# control_avr_rev_a.net
KiCad netlist of a schematic drawn in EAGLE
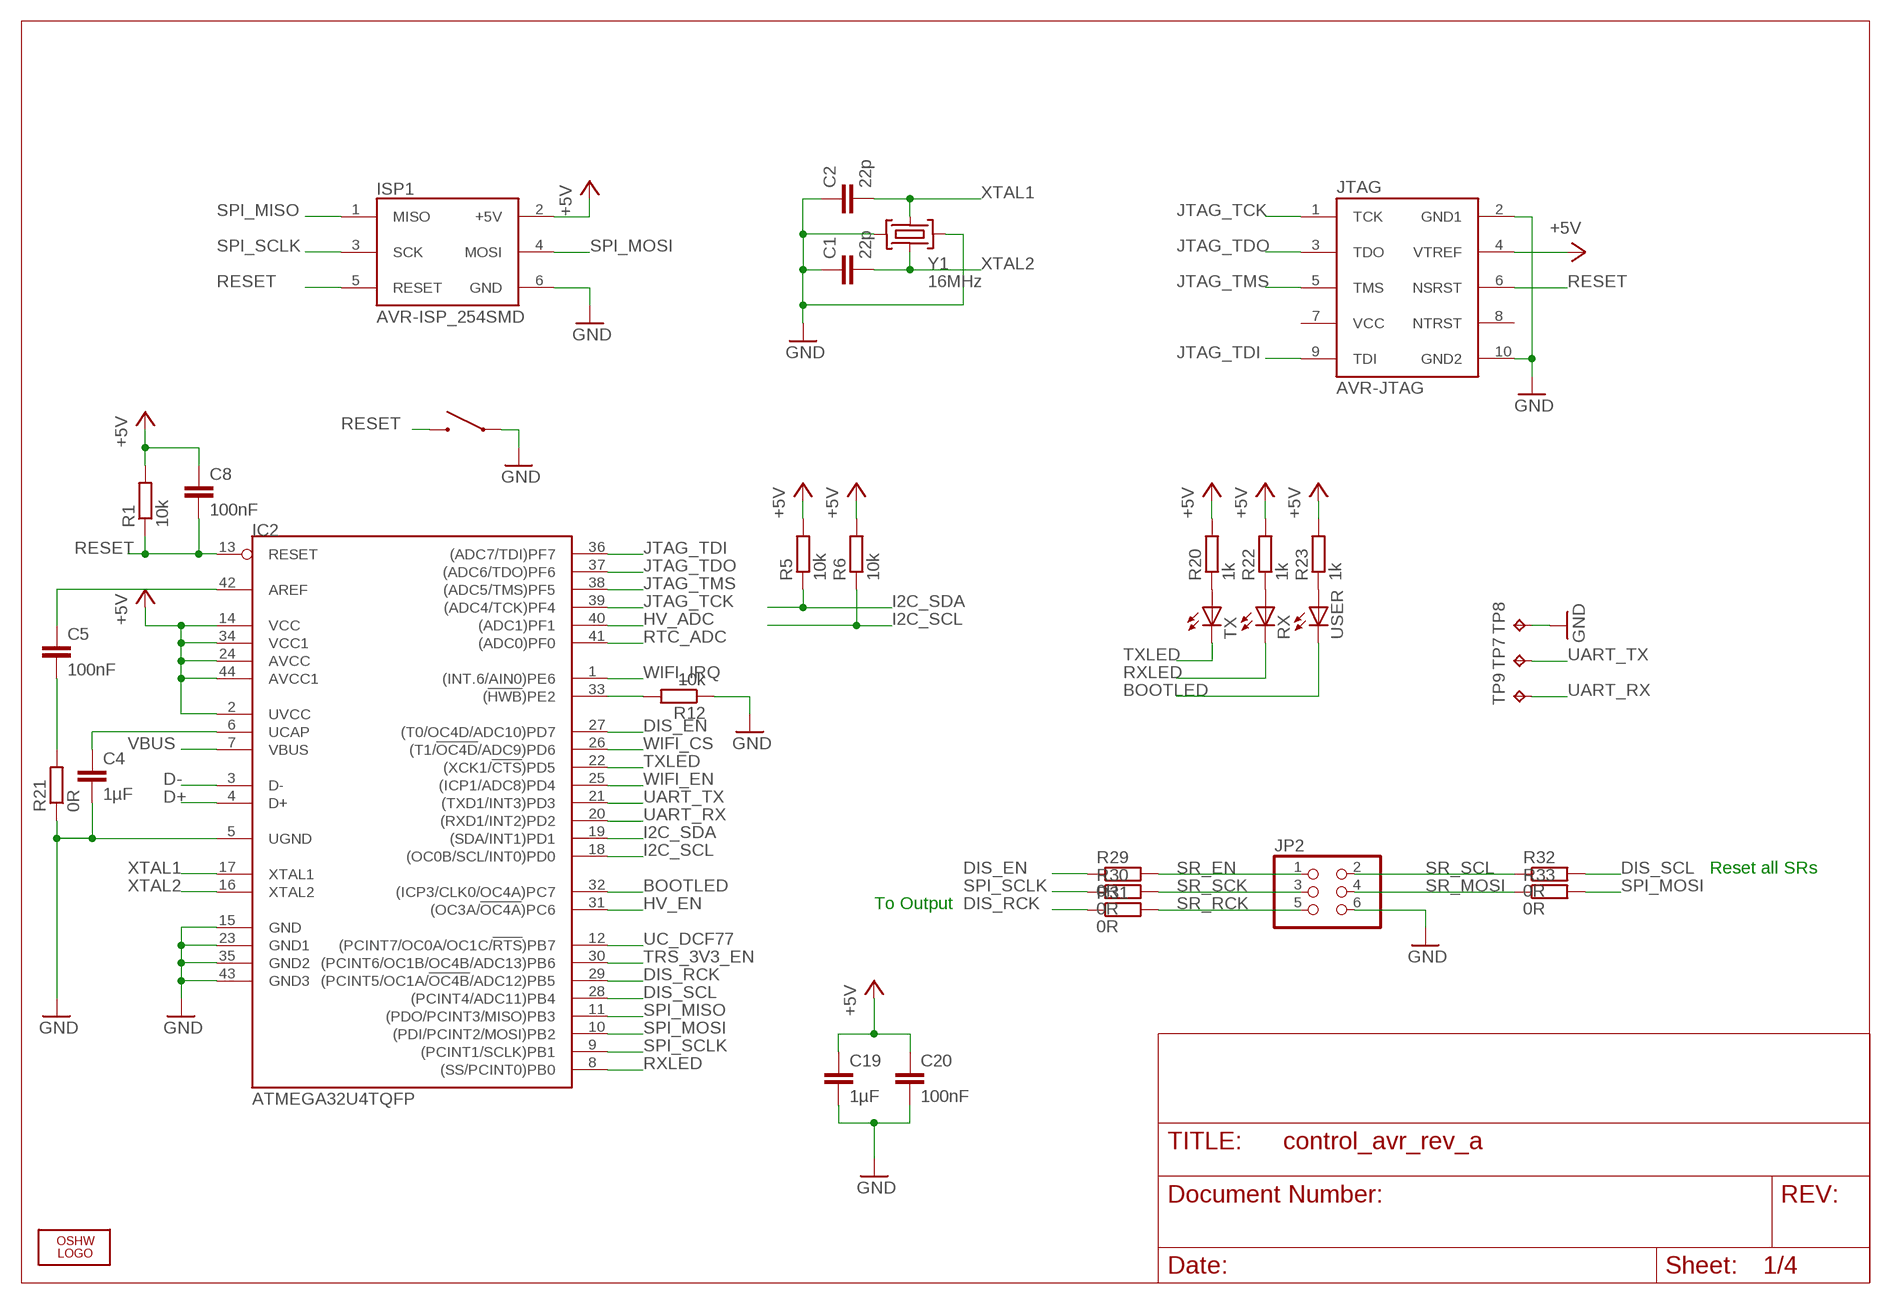
[diagram p0: schematic, sheet 1]
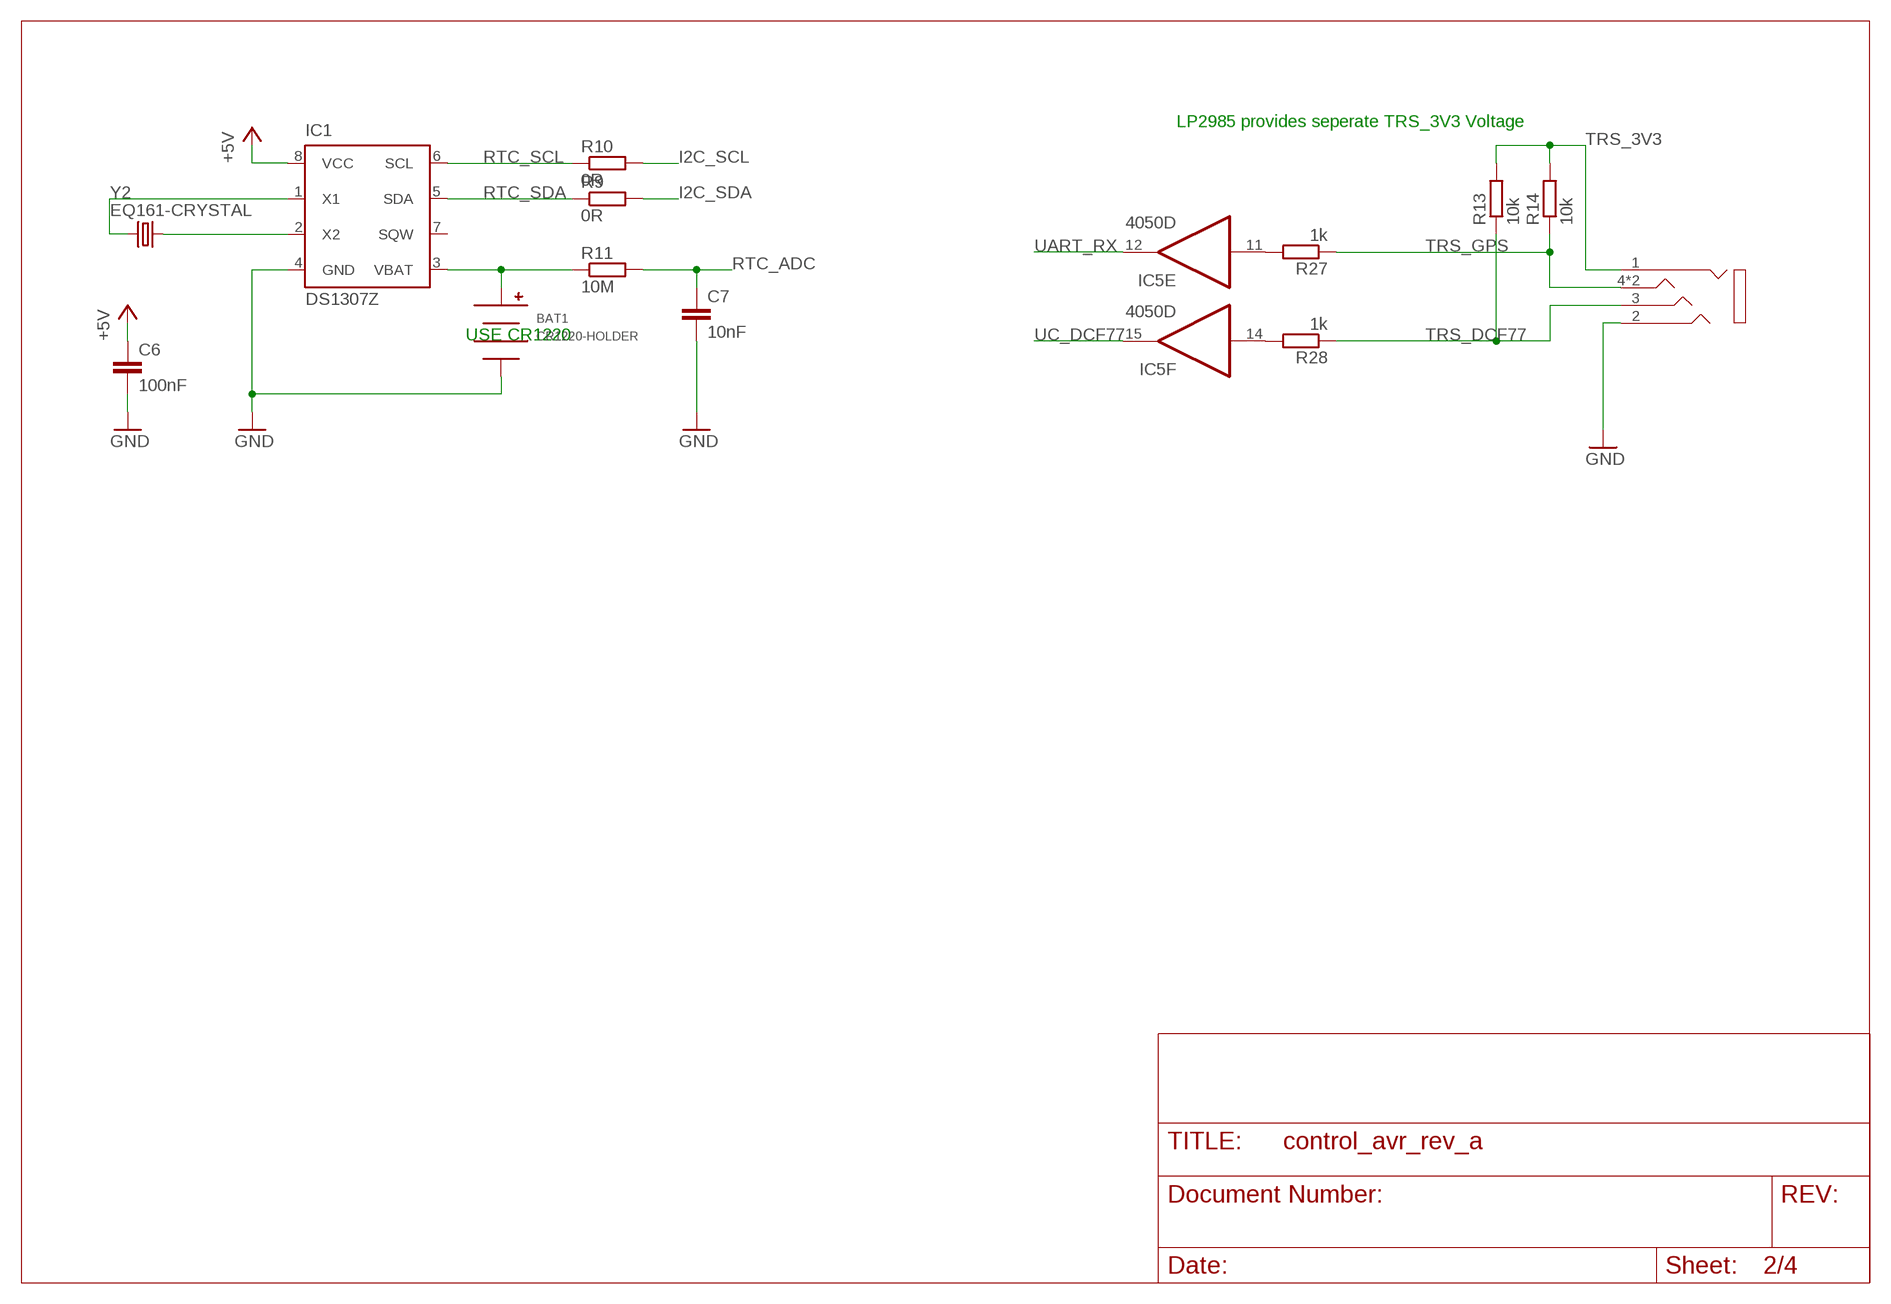
[diagram p1: schematic, sheet 2]
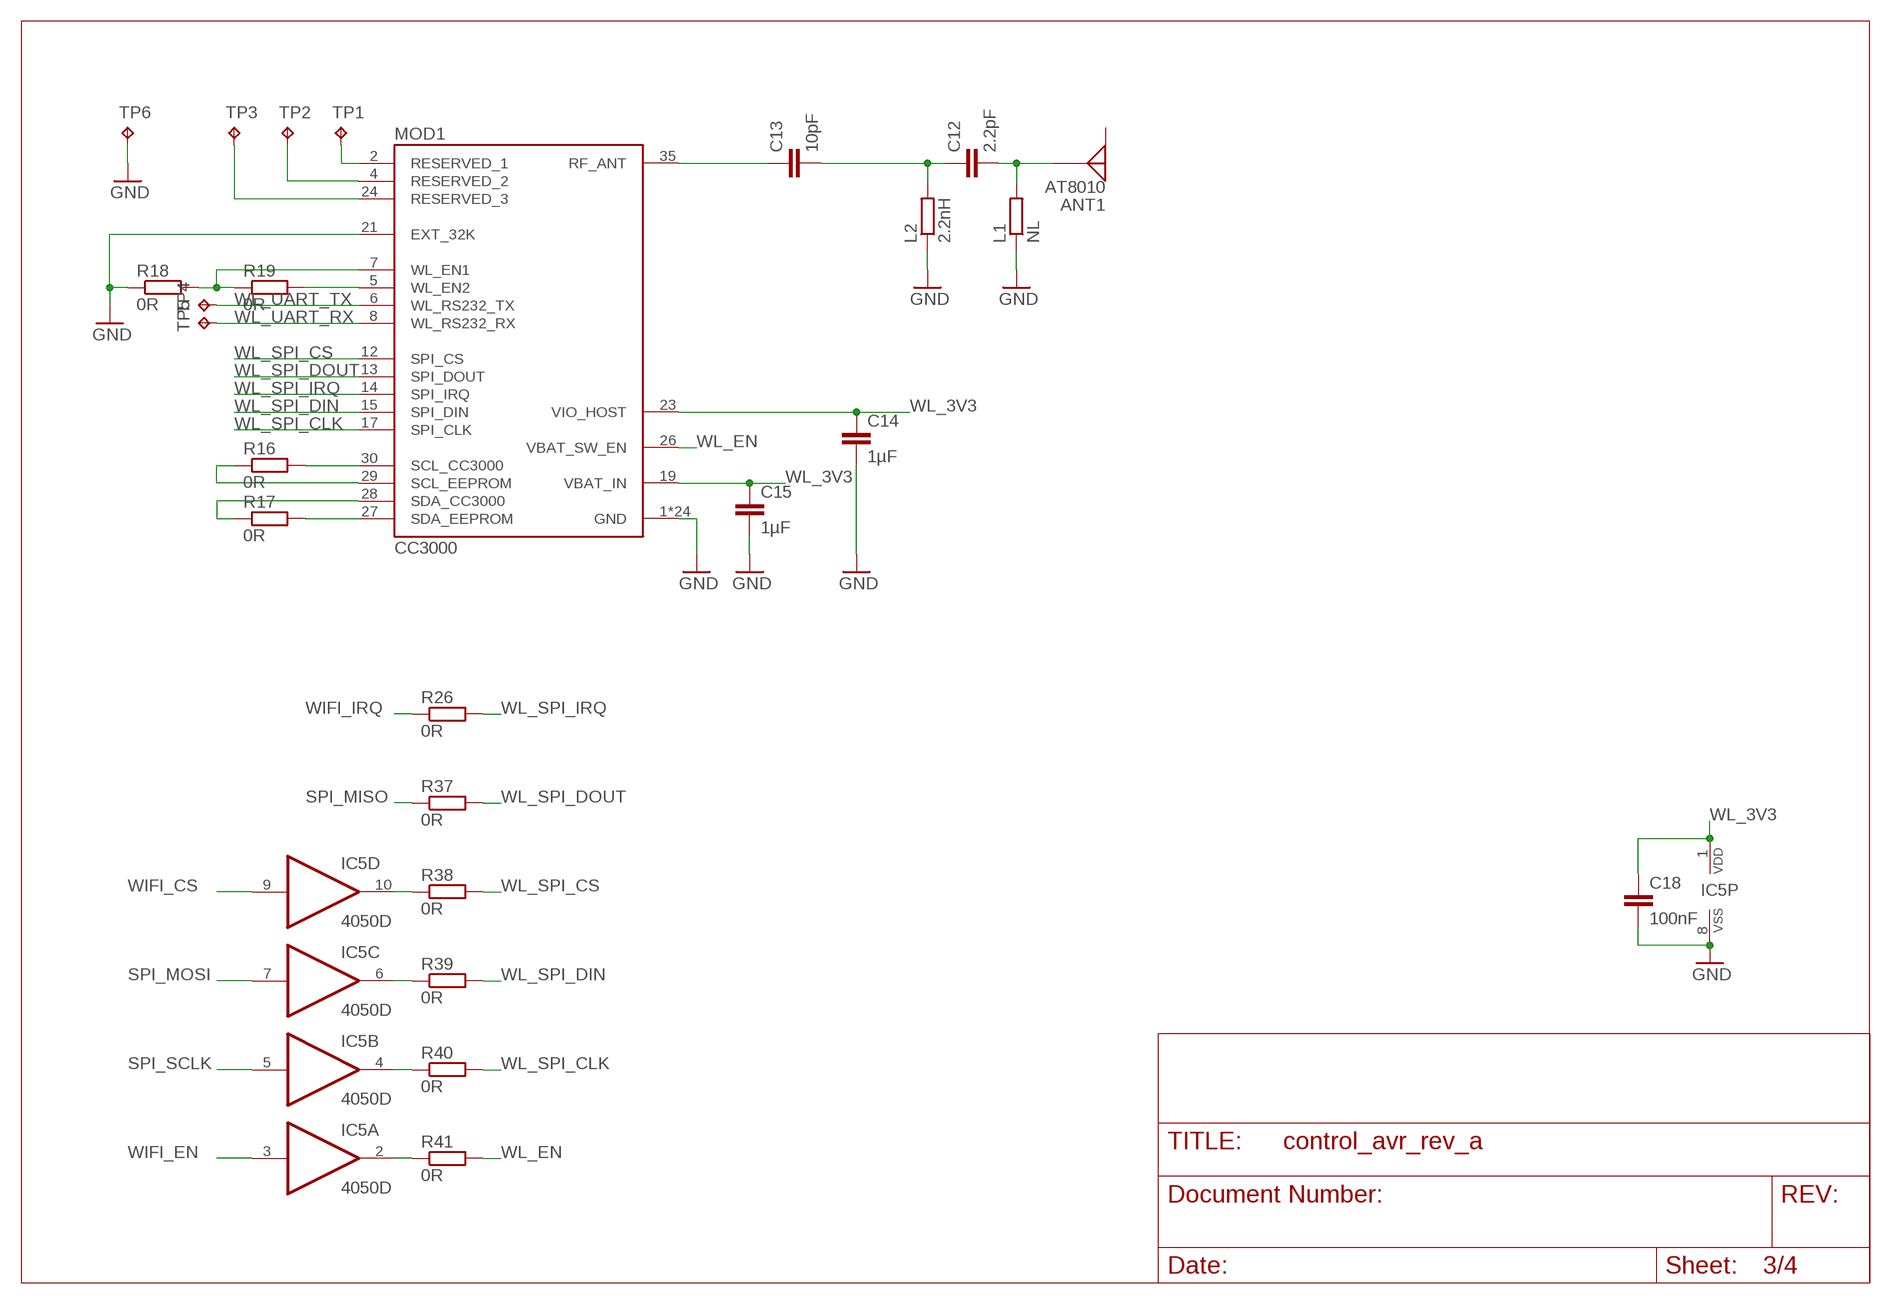
[diagram p2: schematic, sheet 3]
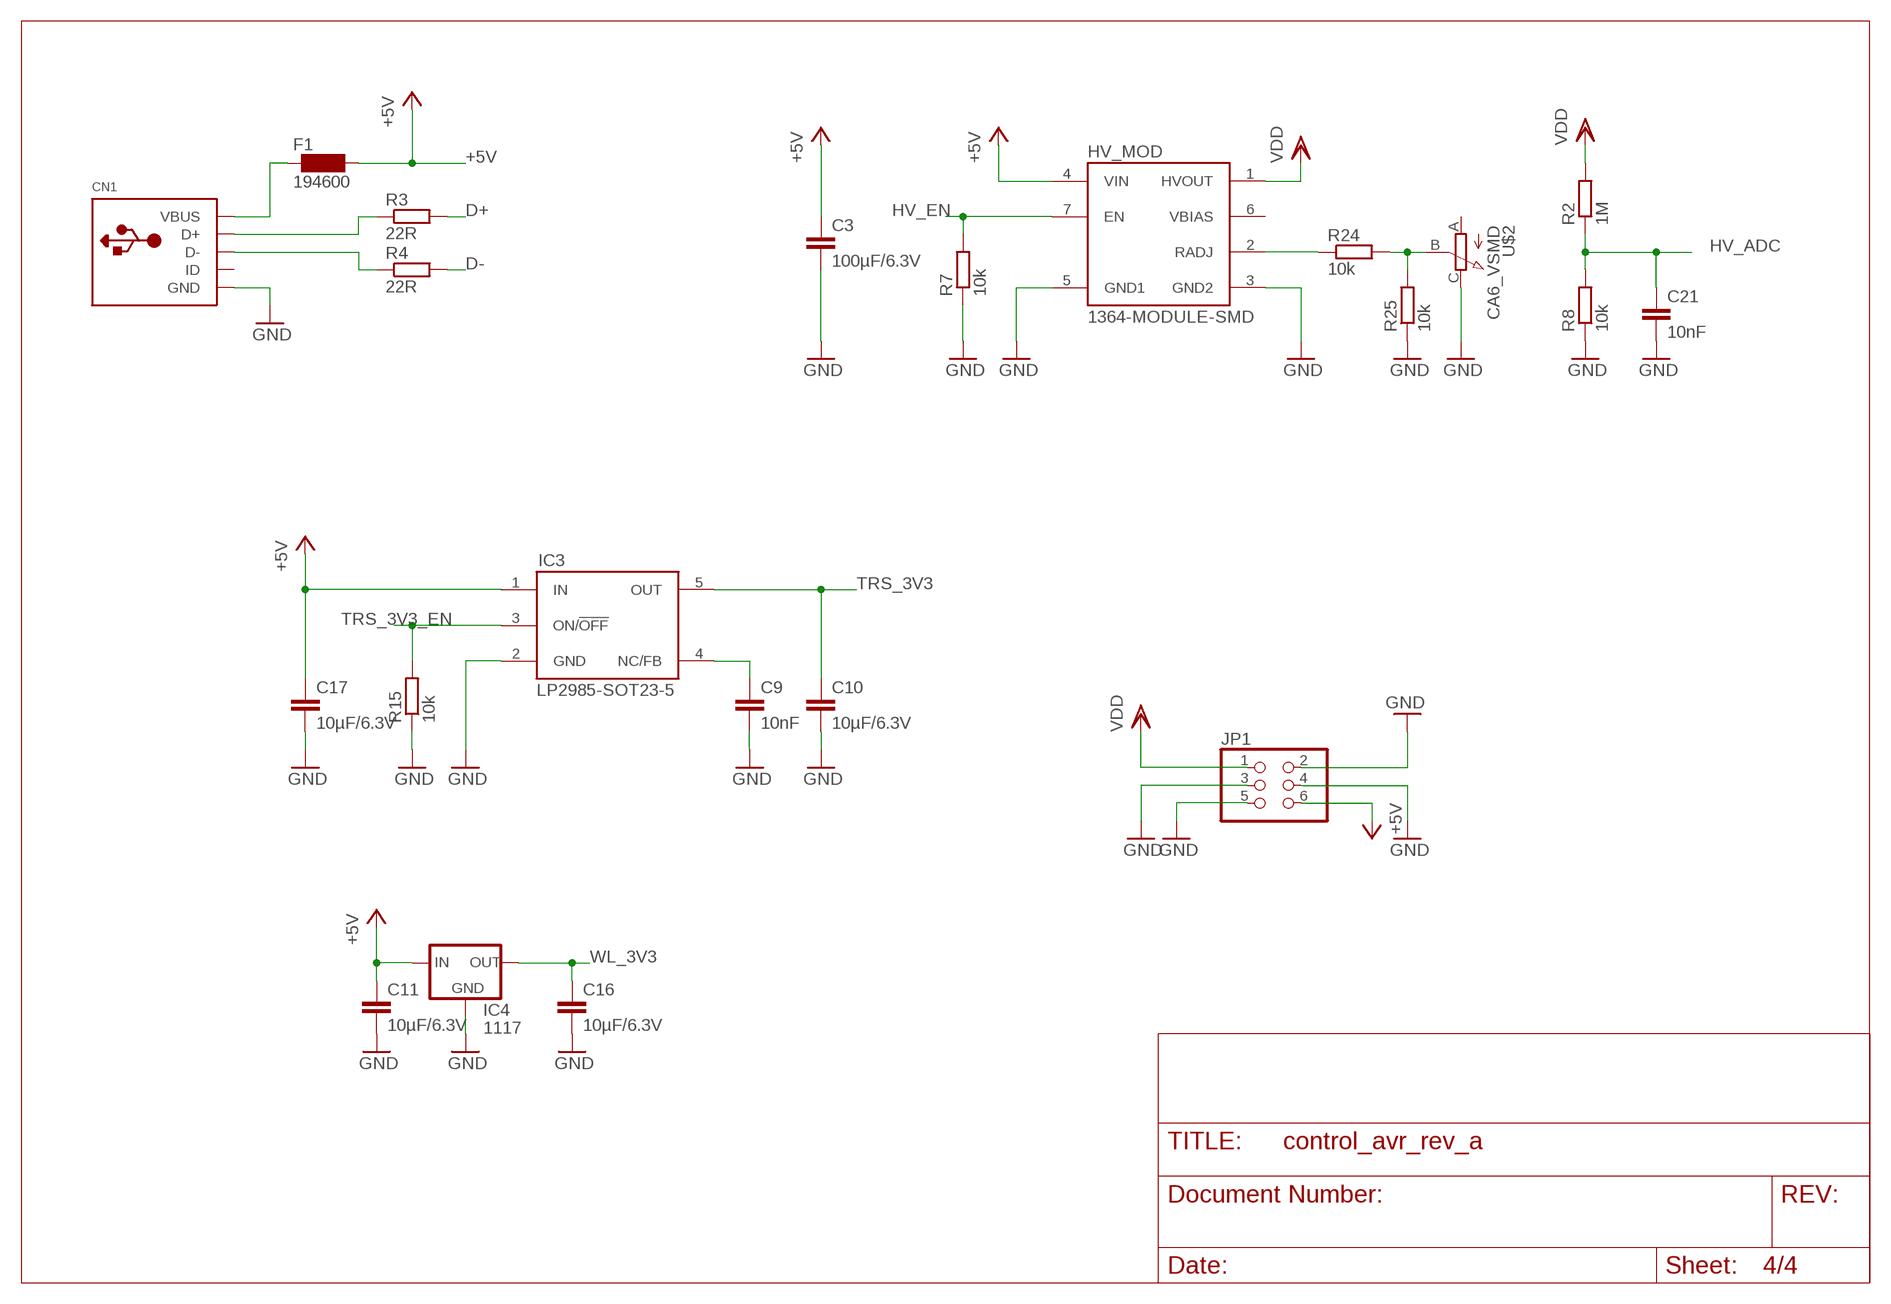
[diagram p3: schematic, sheet 4]

(export (version "E")
  (design (tool "Eeschema 10.0.6"))
  (components
    (comp (ref "C3")
      (value "100µF/6.3V")
      (footprint "eagle-import:C1210")
      (libsource (lib "eagle-import") (part "C-EUC1210"))
    )
    (comp (ref "C9")
      (value "10nF")
      (footprint "eagle-import:C0603")
      (libsource (lib "eagle-import") (part "C-EUC0603"))
    )
    (comp (ref "C10")
      (value "10µF/6.3V")
      (footprint "eagle-import:C0603")
      (libsource (lib "eagle-import") (part "C-EUC0603"))
    )
    (comp (ref "C11")
      (value "10µF/6.3V")
      (footprint "eagle-import:C0603")
      (libsource (lib "eagle-import") (part "C-EUC0603"))
    )
    (comp (ref "C16")
      (value "10µF/6.3V")
      (footprint "eagle-import:C0603")
      (libsource (lib "eagle-import") (part "C-EUC0603"))
    )
    (comp (ref "C17")
      (value "10µF/6.3V")
      (footprint "eagle-import:C0603")
      (libsource (lib "eagle-import") (part "C-EUC0603"))
    )
    (comp (ref "C21")
      (value "10nF")
      (footprint "eagle-import:C0603")
      (libsource (lib "eagle-import") (part "C-EUC0603"))
    )
    (comp (ref "CN1")
      (value "USBMINIB")
      (footprint "eagle-import:USB-MINIB")
      (libsource (lib "eagle-import") (part "USBMINIB"))
    )
    (comp (ref "F1")
      (value "194600")
      (footprint "eagle-import:1812")
      (libsource (lib "eagle-import") (part "194600"))
    )
    (comp (ref "HV_MOD")
      (value "1364-MODULE-SMD")
      (footprint "eagle-import:1364-SMD")
      (libsource (lib "eagle-import") (part "1364-MODULE-SMD"))
    )
    (comp (ref "IC3")
      (value "LP2985-SOT23-5")
      (footprint "eagle-import:SOT23-5")
      (libsource (lib "eagle-import") (part "LP2985-SOT23-5"))
    )
    (comp (ref "IC4")
      (value "1117")
      (footprint "eagle-import:SOT223")
      (libsource (lib "eagle-import") (part "1117"))
    )
    (comp (ref "JP1")
      (value "PINHD-2X3_2.54-SMD-R")
      (footprint "eagle-import:2X03SMD_R")
      (libsource (lib "eagle-import") (part "PINHD-2X3_2.54-SMD-R"))
    )
    (comp (ref "R2")
      (value "1M")
      (footprint "eagle-import:R1206")
      (libsource (lib "eagle-import") (part "R-EU_R1206"))
    )
    (comp (ref "R3")
      (value "22R")
      (footprint "eagle-import:R0603")
      (libsource (lib "eagle-import") (part "R-EU_R0603"))
    )
    (comp (ref "R4")
      (value "22R")
      (footprint "eagle-import:R0603")
      (libsource (lib "eagle-import") (part "R-EU_R0603"))
    )
    (comp (ref "R7")
      (value "10k")
      (footprint "eagle-import:R0603")
      (libsource (lib "eagle-import") (part "R-EU_R0603"))
    )
    (comp (ref "R8")
      (value "10k")
      (footprint "eagle-import:R0603")
      (libsource (lib "eagle-import") (part "R-EU_R0603"))
    )
    (comp (ref "R15")
      (value "10k")
      (footprint "eagle-import:R0603")
      (libsource (lib "eagle-import") (part "R-EU_R0603"))
    )
    (comp (ref "R24")
      (value "10k")
      (footprint "eagle-import:R0603")
      (libsource (lib "eagle-import") (part "R-EU_R0603"))
    )
    (comp (ref "R25")
      (value "10k")
      (footprint "eagle-import:R0603")
      (libsource (lib "eagle-import") (part "R-EU_R0603"))
    )
    (comp (ref "U$2")
      (value "CA6_VSMD")
      (footprint "eagle-import:CA6-VSMD")
      (libsource (lib "eagle-import") (part "CA6_VSMD"))
    )
    (comp (ref "ANT1")
      (value "AT8010")
      (footprint "eagle-import:AT8010")
      (libsource (lib "eagle-import") (part "AT8010"))
    )
    (comp (ref "C12")
      (value "2.2pF")
      (footprint "eagle-import:C0402")
      (libsource (lib "eagle-import") (part "C-EUC0402"))
    )
    (comp (ref "C13")
      (value "10pF")
      (footprint "eagle-import:C0402")
      (libsource (lib "eagle-import") (part "C-EUC0402"))
    )
    (comp (ref "C14")
      (value "1µF")
      (footprint "eagle-import:C0603")
      (libsource (lib "eagle-import") (part "C-EUC0603"))
    )
    (comp (ref "C15")
      (value "1µF")
      (footprint "eagle-import:C0603")
      (libsource (lib "eagle-import") (part "C-EUC0603"))
    )
    (comp (ref "C18")
      (value "100nF")
      (footprint "eagle-import:C0603")
      (libsource (lib "eagle-import") (part "C-EUC0603"))
    )
    (comp (ref "IC5")
      (value "4050D")
      (footprint "eagle-import:SO16")
      (libsource (lib "eagle-import") (part "4050D"))
    )
    (comp (ref "L1")
      (value "NL")
      (footprint "eagle-import:R0402")
      (libsource (lib "eagle-import") (part "R-EU_R0402"))
    )
    (comp (ref "L2")
      (value "2.2nH")
      (footprint "eagle-import:R0402")
      (libsource (lib "eagle-import") (part "R-EU_R0402"))
    )
    (comp (ref "MOD1")
      (value "CC3000")
      (footprint "eagle-import:CC3000")
      (libsource (lib "eagle-import") (part "CC3000"))
    )
    (comp (ref "R16")
      (value "0R")
      (footprint "eagle-import:R0603")
      (libsource (lib "eagle-import") (part "R-EU_R0603"))
    )
    (comp (ref "R17")
      (value "0R")
      (footprint "eagle-import:R0603")
      (libsource (lib "eagle-import") (part "R-EU_R0603"))
    )
    (comp (ref "R18")
      (value "0R")
      (footprint "eagle-import:R0603")
      (libsource (lib "eagle-import") (part "R-EU_R0603"))
    )
    (comp (ref "R19")
      (value "0R")
      (footprint "eagle-import:R0603")
      (libsource (lib "eagle-import") (part "R-EU_R0603"))
    )
    (comp (ref "R26")
      (value "0R")
      (footprint "eagle-import:R0603")
      (libsource (lib "eagle-import") (part "R-EU_R0603"))
    )
    (comp (ref "R37")
      (value "0R")
      (footprint "eagle-import:R0603")
      (libsource (lib "eagle-import") (part "R-EU_R0603"))
    )
    (comp (ref "R38")
      (value "0R")
      (footprint "eagle-import:R0603")
      (libsource (lib "eagle-import") (part "R-EU_R0603"))
    )
    (comp (ref "R39")
      (value "0R")
      (footprint "eagle-import:R0603")
      (libsource (lib "eagle-import") (part "R-EU_R0603"))
    )
    (comp (ref "R40")
      (value "0R")
      (footprint "eagle-import:R0603")
      (libsource (lib "eagle-import") (part "R-EU_R0603"))
    )
    (comp (ref "R41")
      (value "0R")
      (footprint "eagle-import:R0603")
      (libsource (lib "eagle-import") (part "R-EU_R0603"))
    )
    (comp (ref "TP1")
      (value "TPTP06R")
      (footprint "eagle-import:TP06R")
      (libsource (lib "eagle-import") (part "TPTP06R"))
    )
    (comp (ref "TP2")
      (value "TPTP06R")
      (footprint "eagle-import:TP06R")
      (libsource (lib "eagle-import") (part "TPTP06R"))
    )
    (comp (ref "TP3")
      (value "TPTP06R")
      (footprint "eagle-import:TP06R")
      (libsource (lib "eagle-import") (part "TPTP06R"))
    )
    (comp (ref "TP4")
      (value "TPTP10R")
      (footprint "eagle-import:TP10R")
      (libsource (lib "eagle-import") (part "TPTP10R"))
    )
    (comp (ref "TP5")
      (value "TPTP10R")
      (footprint "eagle-import:TP10R")
      (libsource (lib "eagle-import") (part "TPTP10R"))
    )
    (comp (ref "TP6")
      (value "TPTP10SQ")
      (footprint "eagle-import:TP10SQ")
      (libsource (lib "eagle-import") (part "TPTP10SQ"))
    )
    (comp (ref "BAT1")
      (value "CR1220-HOLDER")
      (footprint "eagle-import:HARWIN-CR1220")
      (libsource (lib "eagle-import") (part "CR1220-HOLDER"))
    )
    (comp (ref "C6")
      (value "100nF")
      (footprint "eagle-import:C0603")
      (libsource (lib "eagle-import") (part "C-EUC0603"))
    )
    (comp (ref "C7")
      (value "10nF")
      (footprint "eagle-import:C0603")
      (libsource (lib "eagle-import") (part "C-EUC0603"))
    )
    (comp (ref "IC1")
      (value "DS1307Z")
      (footprint "eagle-import:SOIC8")
      (libsource (lib "eagle-import") (part "DS1307Z"))
    )
    (comp (ref "R9")
      (value "0R")
      (footprint "eagle-import:R0603")
      (libsource (lib "eagle-import") (part "R-EU_R0603"))
    )
    (comp (ref "R10")
      (value "0R")
      (footprint "eagle-import:R0603")
      (libsource (lib "eagle-import") (part "R-EU_R0603"))
    )
    (comp (ref "R11")
      (value "10M")
      (footprint "eagle-import:R0603")
      (libsource (lib "eagle-import") (part "R-EU_R0603"))
    )
    (comp (ref "R13")
      (value "10k")
      (footprint "eagle-import:R0603")
      (libsource (lib "eagle-import") (part "R-EU_R0603"))
    )
    (comp (ref "R14")
      (value "10k")
      (footprint "eagle-import:R0603")
      (libsource (lib "eagle-import") (part "R-EU_R0603"))
    )
    (comp (ref "R27")
      (value "1k")
      (footprint "eagle-import:R0603")
      (libsource (lib "eagle-import") (part "R-EU_R0603"))
    )
    (comp (ref "R28")
      (value "1k")
      (footprint "eagle-import:R0603")
      (libsource (lib "eagle-import") (part "R-EU_R0603"))
    )
    (comp (ref "U$3")
      (value "1503_13")
      (footprint "eagle-import:1503-03")
      (libsource (lib "eagle-import") (part "1503_13"))
    )
    (comp (ref "Y2")
      (value "EQ161-CRYSTAL")
      (footprint "eagle-import:EQ161")
      (libsource (lib "eagle-import") (part "EQ161-CRYSTAL"))
    )
    (comp (ref "C1")
      (value "22p")
      (footprint "eagle-import:C0603")
      (libsource (lib "eagle-import") (part "C-EUC0603"))
    )
    (comp (ref "C2")
      (value "22p")
      (footprint "eagle-import:C0603")
      (libsource (lib "eagle-import") (part "C-EUC0603"))
    )
    (comp (ref "C4")
      (value "1µF")
      (footprint "eagle-import:C0603")
      (libsource (lib "eagle-import") (part "C-EUC0603"))
    )
    (comp (ref "C5")
      (value "100nF")
      (footprint "eagle-import:C0603")
      (libsource (lib "eagle-import") (part "C-EUC0603"))
    )
    (comp (ref "C8")
      (value "100nF")
      (footprint "eagle-import:C0603")
      (libsource (lib "eagle-import") (part "C-EUC0603"))
    )
    (comp (ref "C19")
      (value "1µF")
      (footprint "eagle-import:C0603")
      (libsource (lib "eagle-import") (part "C-EUC0603"))
    )
    (comp (ref "C20")
      (value "100nF")
      (footprint "eagle-import:C0603")
      (libsource (lib "eagle-import") (part "C-EUC0603"))
    )
    (comp (ref "IC2")
      (value "ATMEGA32U4TQFP")
      (footprint "eagle-import:TQFP44")
      (libsource (lib "eagle-import") (part "ATMEGA32U4TQFP"))
    )
    (comp (ref "ISP1")
      (value "AVR-ISP_254SMD")
      (footprint "eagle-import:2X03SMD")
      (libsource (lib "eagle-import") (part "AVR-ISP_254SMD"))
    )
    (comp (ref "JP2")
      (value "PINHD-2X3_2.54-SMD-R")
      (footprint "eagle-import:2X03SMD_R")
      (libsource (lib "eagle-import") (part "PINHD-2X3_2.54-SMD-R"))
    )
    (comp (ref "JTAG")
      (value "AVR-JTAG")
      (footprint "eagle-import:20021121-10010XXLF")
      (libsource (lib "eagle-import") (part "AVR-JTAG"))
    )
    (comp (ref "LOGO1")
      (value "OSHW_LOGO_FILLX0200-NT")
      (footprint "eagle-import:OSHW_FILLX200_NOTEXT")
      (libsource (lib "eagle-import") (part "OSHW_LOGO_FILLX0200-NT"))
    )
    (comp (ref "R1")
      (value "10k")
      (footprint "eagle-import:R0603")
      (libsource (lib "eagle-import") (part "R-EU_R0603"))
    )
    (comp (ref "R5")
      (value "10k")
      (footprint "eagle-import:R0603")
      (libsource (lib "eagle-import") (part "R-EU_R0603"))
    )
    (comp (ref "R6")
      (value "10k")
      (footprint "eagle-import:R0603")
      (libsource (lib "eagle-import") (part "R-EU_R0603"))
    )
    (comp (ref "R12")
      (value "10k")
      (footprint "eagle-import:R0603")
      (libsource (lib "eagle-import") (part "R-EU_R0603"))
    )
    (comp (ref "R20")
      (value "1k")
      (footprint "eagle-import:R0603")
      (libsource (lib "eagle-import") (part "R-EU_R0603"))
    )
    (comp (ref "R21")
      (value "0R")
      (footprint "eagle-import:R0603")
      (libsource (lib "eagle-import") (part "R-EU_R0603"))
    )
    (comp (ref "R22")
      (value "1k")
      (footprint "eagle-import:R0603")
      (libsource (lib "eagle-import") (part "R-EU_R0603"))
    )
    (comp (ref "R23")
      (value "1k")
      (footprint "eagle-import:R0603")
      (libsource (lib "eagle-import") (part "R-EU_R0603"))
    )
    (comp (ref "R29")
      (value "0R")
      (footprint "eagle-import:R0603")
      (libsource (lib "eagle-import") (part "R-EU_R0603"))
    )
    (comp (ref "R30")
      (value "0R")
      (footprint "eagle-import:R0603")
      (libsource (lib "eagle-import") (part "R-EU_R0603"))
    )
    (comp (ref "R31")
      (value "0R")
      (footprint "eagle-import:R0603")
      (libsource (lib "eagle-import") (part "R-EU_R0603"))
    )
    (comp (ref "R32")
      (value "0R")
      (footprint "eagle-import:R0603")
      (libsource (lib "eagle-import") (part "R-EU_R0603"))
    )
    (comp (ref "R33")
      (value "0R")
      (footprint "eagle-import:R0603")
      (libsource (lib "eagle-import") (part "R-EU_R0603"))
    )
    (comp (ref "RESET")
      (value "TACT-SWITCH-47-35")
      (footprint "eagle-import:47-35")
      (libsource (lib "eagle-import") (part "TACT-SWITCH-47-35"))
    )
    (comp (ref "RX")
      (value "LEDCHIP-LED0603")
      (footprint "eagle-import:CHIP-LED0603")
      (libsource (lib "eagle-import") (part "LEDCHIP-LED0603"))
    )
    (comp (ref "TP7")
      (value "TPTP10R")
      (footprint "eagle-import:TP10R")
      (libsource (lib "eagle-import") (part "TPTP10R"))
    )
    (comp (ref "TP8")
      (value "TPTP10SQ")
      (footprint "eagle-import:TP10SQ")
      (libsource (lib "eagle-import") (part "TPTP10SQ"))
    )
    (comp (ref "TP9")
      (value "TPTP10R")
      (footprint "eagle-import:TP10R")
      (libsource (lib "eagle-import") (part "TPTP10R"))
    )
    (comp (ref "TX")
      (value "LEDCHIP-LED0603")
      (footprint "eagle-import:CHIP-LED0603")
      (libsource (lib "eagle-import") (part "LEDCHIP-LED0603"))
    )
    (comp (ref "USER")
      (value "LEDCHIP-LED0603")
      (footprint "eagle-import:CHIP-LED0603")
      (libsource (lib "eagle-import") (part "LEDCHIP-LED0603"))
    )
    (comp (ref "Y1")
      (value "16MHz")
      (footprint "eagle-import:X22")
      (libsource (lib "eagle-import") (part "X22-CRYSTAL"))
    )
  )
  (nets
    (net (code "1") (name "+5V") (class "Default")
      (node (ref "C11") (pin "1") (pinfunction "1_1") (pintype "passive"))
      (node (ref "C17") (pin "1") (pinfunction "1_1") (pintype "passive"))
      (node (ref "C19") (pin "1") (pinfunction "1_1") (pintype "passive"))
      (node (ref "C20") (pin "1") (pinfunction "1_1") (pintype "passive"))
      (node (ref "C3") (pin "1") (pinfunction "1_1") (pintype "passive"))
      (node (ref "C6") (pin "1") (pinfunction "1_1") (pintype "passive"))
      (node (ref "C8") (pin "1") (pinfunction "1_1") (pintype "passive"))
      (node (ref "F1") (pin "P$2") (pinfunction "P$2_P$2") (pintype "bidirectional"))
      (node (ref "HV_MOD") (pin "4") (pinfunction "VIN_4") (pintype "bidirectional"))
      (node (ref "IC1") (pin "8") (pinfunction "VCC_8") (pintype "power_in"))
      (node (ref "IC2") (pin "14") (pinfunction "VCC_14") (pintype "bidirectional"))
      (node (ref "IC2") (pin "2") (pinfunction "UVCC_2") (pintype "bidirectional"))
      (node (ref "IC2") (pin "24") (pinfunction "AVCC_24") (pintype "bidirectional"))
      (node (ref "IC2") (pin "34") (pinfunction "VCC1_34") (pintype "bidirectional"))
      (node (ref "IC2") (pin "44") (pinfunction "AVCC1_44") (pintype "bidirectional"))
      (node (ref "IC3") (pin "1") (pinfunction "IN_1") (pintype "bidirectional"))
      (node (ref "IC4") (pin "3") (pinfunction "IN_3") (pintype "input"))
      (node (ref "ISP1") (pin "2") (pinfunction "+5V_2") (pintype "bidirectional"))
      (node (ref "JP1") (pin "6") (pinfunction "6_6") (pintype "passive"))
      (node (ref "JTAG") (pin "4") (pinfunction "VTREF_4") (pintype "bidirectional"))
      (node (ref "R1") (pin "2") (pinfunction "2_2") (pintype "passive"))
      (node (ref "R20") (pin "2") (pinfunction "2_2") (pintype "passive"))
      (node (ref "R22") (pin "2") (pinfunction "2_2") (pintype "passive"))
      (node (ref "R23") (pin "2") (pinfunction "2_2") (pintype "passive"))
      (node (ref "R5") (pin "2") (pinfunction "2_2") (pintype "passive"))
      (node (ref "R6") (pin "2") (pinfunction "2_2") (pintype "passive"))
    )
    (net (code "2") (name "BOOTLED") (class "Default")
      (node (ref "IC2") (pin "32") (pinfunction "(ICP3/CLK0/OC4A)PC7_32") (pintype "bidirectional"))
      (node (ref "USER") (pin "C") (pinfunction "C_C") (pintype "passive"))
    )
    (net (code "3") (name "D+") (class "Default")
      (node (ref "IC2") (pin "4") (pinfunction "D+_4") (pintype "bidirectional"))
      (node (ref "R3") (pin "2") (pinfunction "2_2") (pintype "passive"))
    )
    (net (code "4") (name "D-") (class "Default")
      (node (ref "IC2") (pin "3") (pinfunction "D-_3") (pintype "bidirectional"))
      (node (ref "R4") (pin "2") (pinfunction "2_2") (pintype "passive"))
    )
    (net (code "5") (name "DIS_EN") (class "Default")
      (node (ref "IC2") (pin "27") (pinfunction "(T0/OC4D/ADC10)PD7_27") (pintype "bidirectional"))
      (node (ref "R29") (pin "1") (pinfunction "1_1") (pintype "passive"))
    )
    (net (code "6") (name "DIS_RCK") (class "Default")
      (node (ref "IC2") (pin "29") (pinfunction "(PCINT5/OC1A/~{OC4B}/ADC12)PB5_29") (pintype "bidirectional"))
      (node (ref "R31") (pin "1") (pinfunction "1_1") (pintype "passive"))
    )
    (net (code "7") (name "DIS_SCL") (class "Default")
      (node (ref "IC2") (pin "28") (pinfunction "(PCINT4/ADC11)PB4_28") (pintype "bidirectional"))
      (node (ref "R32") (pin "2") (pinfunction "2_2") (pintype "passive"))
    )
    (net (code "8") (name "GND") (class "Default")
      (node (ref "BAT1") (pin "NEG") (pinfunction "NEG_NEG") (pintype "bidirectional"))
      (node (ref "C1") (pin "1") (pinfunction "1_1") (pintype "passive"))
      (node (ref "C10") (pin "2") (pinfunction "2_2") (pintype "passive"))
      (node (ref "C11") (pin "2") (pinfunction "2_2") (pintype "passive"))
      (node (ref "C14") (pin "2") (pinfunction "2_2") (pintype "passive"))
      (node (ref "C15") (pin "2") (pinfunction "2_2") (pintype "passive"))
      (node (ref "C16") (pin "2") (pinfunction "2_2") (pintype "passive"))
      (node (ref "C17") (pin "2") (pinfunction "2_2") (pintype "passive"))
      (node (ref "C18") (pin "2") (pinfunction "2_2") (pintype "passive"))
      (node (ref "C19") (pin "2") (pinfunction "2_2") (pintype "passive"))
      (node (ref "C2") (pin "1") (pinfunction "1_1") (pintype "passive"))
      (node (ref "C20") (pin "2") (pinfunction "2_2") (pintype "passive"))
      (node (ref "C21") (pin "2") (pinfunction "2_2") (pintype "passive"))
      (node (ref "C3") (pin "2") (pinfunction "2_2") (pintype "passive"))
      (node (ref "C4") (pin "2") (pinfunction "2_2") (pintype "passive"))
      (node (ref "C6") (pin "2") (pinfunction "2_2") (pintype "passive"))
      (node (ref "C7") (pin "2") (pinfunction "2_2") (pintype "passive"))
      (node (ref "C9") (pin "2") (pinfunction "2_2") (pintype "passive"))
      (node (ref "CN1") (pin "GND") (pinfunction "GND_GND") (pintype "power_in"))
      (node (ref "HV_MOD") (pin "3") (pinfunction "GND2_3") (pintype "bidirectional"))
      (node (ref "HV_MOD") (pin "5") (pinfunction "GND1_5") (pintype "bidirectional"))
      (node (ref "IC1") (pin "4") (pinfunction "GND_4") (pintype "power_in"))
      (node (ref "IC2") (pin "15") (pinfunction "GND_15") (pintype "bidirectional"))
      (node (ref "IC2") (pin "23") (pinfunction "GND1_23") (pintype "bidirectional"))
      (node (ref "IC2") (pin "35") (pinfunction "GND2_35") (pintype "bidirectional"))
      (node (ref "IC2") (pin "43") (pinfunction "GND3_43") (pintype "bidirectional"))
      (node (ref "IC2") (pin "5") (pinfunction "UGND_5") (pintype "bidirectional"))
      (node (ref "IC3") (pin "2") (pinfunction "GND_2") (pintype "bidirectional"))
      (node (ref "IC4") (pin "1") (pinfunction "GND_1") (pintype "input"))
      (node (ref "IC5") (pin "8") (pinfunction "VSS_8") (pintype "power_in"))
      (node (ref "ISP1") (pin "6") (pinfunction "GND_6") (pintype "bidirectional"))
      (node (ref "JP1") (pin "2") (pinfunction "2_2") (pintype "passive"))
      (node (ref "JP1") (pin "3") (pinfunction "3_3") (pintype "passive"))
      (node (ref "JP1") (pin "4") (pinfunction "4_4") (pintype "passive"))
      (node (ref "JP1") (pin "5") (pinfunction "5_5") (pintype "passive"))
      (node (ref "JP2") (pin "6") (pinfunction "6_6") (pintype "passive"))
      (node (ref "JTAG") (pin "10") (pinfunction "GND2_10") (pintype "bidirectional"))
      (node (ref "JTAG") (pin "2") (pinfunction "GND1_2") (pintype "bidirectional"))
      (node (ref "L1") (pin "1") (pinfunction "1_1") (pintype "passive"))
      (node (ref "L2") (pin "1") (pinfunction "1_1") (pintype "passive"))
      (node (ref "MOD1") (pin "1") (pinfunction "GND_1") (pintype "bidirectional"))
      (node (ref "MOD1") (pin "10") (pinfunction "GND_10") (pintype "bidirectional"))
      (node (ref "MOD1") (pin "11") (pinfunction "GND_11") (pintype "bidirectional"))
      (node (ref "MOD1") (pin "16") (pinfunction "GND_16") (pintype "bidirectional"))
      (node (ref "MOD1") (pin "18") (pinfunction "GND_18") (pintype "bidirectional"))
      (node (ref "MOD1") (pin "20") (pinfunction "GND_20") (pintype "bidirectional"))
      (node (ref "MOD1") (pin "21") (pinfunction "EXT_32K_21") (pintype "bidirectional"))
      (node (ref "MOD1") (pin "22") (pinfunction "GND_22") (pintype "bidirectional"))
      (node (ref "MOD1") (pin "25") (pinfunction "GND_25") (pintype "bidirectional"))
      (node (ref "MOD1") (pin "31") (pinfunction "GND_31") (pintype "bidirectional"))
      (node (ref "MOD1") (pin "32") (pinfunction "GND_32") (pintype "bidirectional"))
      (node (ref "MOD1") (pin "33") (pinfunction "GND_33") (pintype "bidirectional"))
      (node (ref "MOD1") (pin "34") (pinfunction "GND_34") (pintype "bidirectional"))
      (node (ref "MOD1") (pin "36") (pinfunction "GND_36") (pintype "bidirectional"))
      (node (ref "MOD1") (pin "37") (pinfunction "GND_37") (pintype "bidirectional"))
      (node (ref "MOD1") (pin "38") (pinfunction "GND_38") (pintype "bidirectional"))
      (node (ref "MOD1") (pin "39") (pinfunction "GND_39") (pintype "bidirectional"))
      (node (ref "MOD1") (pin "40") (pinfunction "GND_40") (pintype "bidirectional"))
      (node (ref "MOD1") (pin "41") (pinfunction "GND_41") (pintype "bidirectional"))
      (node (ref "MOD1") (pin "42") (pinfunction "GND_42") (pintype "bidirectional"))
      (node (ref "MOD1") (pin "43") (pinfunction "GND_43") (pintype "bidirectional"))
      (node (ref "MOD1") (pin "44") (pinfunction "GND_44") (pintype "bidirectional"))
      (node (ref "MOD1") (pin "45") (pinfunction "GND_45") (pintype "bidirectional"))
      (node (ref "MOD1") (pin "46") (pinfunction "GND_46") (pintype "bidirectional"))
      (node (ref "MOD1") (pin "9") (pinfunction "GND_9") (pintype "bidirectional"))
      (node (ref "R12") (pin "1") (pinfunction "1_1") (pintype "passive"))
      (node (ref "R15") (pin "1") (pinfunction "1_1") (pintype "passive"))
      (node (ref "R18") (pin "1") (pinfunction "1_1") (pintype "passive"))
      (node (ref "R21") (pin "1") (pinfunction "1_1") (pintype "passive"))
      (node (ref "R25") (pin "1") (pinfunction "1_1") (pintype "passive"))
      (node (ref "R7") (pin "1") (pinfunction "1_1") (pintype "passive"))
      (node (ref "R8") (pin "1") (pinfunction "1_1") (pintype "passive"))
      (node (ref "RESET") (pin "C") (pinfunction "P$2_C") (pintype "bidirectional"))
      (node (ref "RESET") (pin "D") (pinfunction "P$2_D") (pintype "bidirectional"))
      (node (ref "TP6") (pin "TP") (pinfunction "TP_TP") (pintype "input"))
      (node (ref "TP8") (pin "TP") (pinfunction "TP_TP") (pintype "input"))
      (node (ref "U$2") (pin "C") (pinfunction "E_C") (pintype "passive"))
      (node (ref "U$3") (pin "2") (pinfunction "2_2") (pintype "bidirectional"))
      (node (ref "Y1") (pin "P$1") (pinfunction "GND1_P$1") (pintype "bidirectional"))
      (node (ref "Y1") (pin "P$3") (pinfunction "GND2_P$3") (pintype "bidirectional"))
    )
    (net (code "9") (name "HV_ADC") (class "Default")
      (node (ref "C21") (pin "1") (pinfunction "1_1") (pintype "passive"))
      (node (ref "IC2") (pin "40") (pinfunction "(ADC1)PF1_40") (pintype "bidirectional"))
      (node (ref "R2") (pin "1") (pinfunction "1_1") (pintype "passive"))
      (node (ref "R8") (pin "2") (pinfunction "2_2") (pintype "passive"))
    )
    (net (code "10") (name "HV_EN") (class "Default")
      (node (ref "HV_MOD") (pin "7") (pinfunction "EN_7") (pintype "bidirectional"))
      (node (ref "IC2") (pin "31") (pinfunction "(OC3A/~{OC4A})PC6_31") (pintype "bidirectional"))
      (node (ref "R7") (pin "2") (pinfunction "2_2") (pintype "passive"))
    )
    (net (code "11") (name "I2C_SCL") (class "Default")
      (node (ref "IC2") (pin "18") (pinfunction "(OC0B/SCL/INT0)PD0_18") (pintype "bidirectional"))
      (node (ref "R10") (pin "2") (pinfunction "2_2") (pintype "passive"))
      (node (ref "R6") (pin "1") (pinfunction "1_1") (pintype "passive"))
    )
    (net (code "12") (name "I2C_SDA") (class "Default")
      (node (ref "IC2") (pin "19") (pinfunction "(SDA/INT1)PD1_19") (pintype "bidirectional"))
      (node (ref "R5") (pin "1") (pinfunction "1_1") (pintype "passive"))
      (node (ref "R9") (pin "2") (pinfunction "2_2") (pintype "passive"))
    )
    (net (code "13") (name "JTAG_TCK") (class "Default")
      (node (ref "IC2") (pin "39") (pinfunction "(ADC4/TCK)PF4_39") (pintype "bidirectional"))
      (node (ref "JTAG") (pin "1") (pinfunction "TCK_1") (pintype "bidirectional"))
    )
    (net (code "14") (name "JTAG_TDI") (class "Default")
      (node (ref "IC2") (pin "36") (pinfunction "(ADC7/TDI)PF7_36") (pintype "bidirectional"))
      (node (ref "JTAG") (pin "9") (pinfunction "TDI_9") (pintype "bidirectional"))
    )
    (net (code "15") (name "JTAG_TDO") (class "Default")
      (node (ref "IC2") (pin "37") (pinfunction "(ADC6/TDO)PF6_37") (pintype "bidirectional"))
      (node (ref "JTAG") (pin "3") (pinfunction "TDO_3") (pintype "bidirectional"))
    )
    (net (code "16") (name "JTAG_TMS") (class "Default")
      (node (ref "IC2") (pin "38") (pinfunction "(ADC5/TMS)PF5_38") (pintype "bidirectional"))
      (node (ref "JTAG") (pin "5") (pinfunction "TMS_5") (pintype "bidirectional"))
    )
    (net (code "17") (name "Net-(ANT1-PadANT)") (class "Default")
      (node (ref "ANT1") (pin "ANT") (pinfunction "ANT_ANT") (pintype "bidirectional"))
      (node (ref "C12") (pin "2") (pinfunction "2_2") (pintype "passive"))
      (node (ref "L1") (pin "2") (pinfunction "2_2") (pintype "passive"))
    )
    (net (code "18") (name "Net-(C5-Pad2)") (class "Default")
      (node (ref "C5") (pin "2") (pinfunction "2_2") (pintype "passive"))
      (node (ref "R21") (pin "2") (pinfunction "2_2") (pintype "passive"))
    )
    (net (code "19") (name "Net-(C12-Pad1)") (class "Default")
      (node (ref "C12") (pin "1") (pinfunction "1_1") (pintype "passive"))
      (node (ref "C13") (pin "2") (pinfunction "2_2") (pintype "passive"))
      (node (ref "L2") (pin "2") (pinfunction "2_2") (pintype "passive"))
    )
    (net (code "20") (name "Net-(CN1-PadD+)") (class "Default")
      (node (ref "CN1") (pin "D+") (pinfunction "D+_D+") (pintype "bidirectional"))
      (node (ref "R3") (pin "1") (pinfunction "1_1") (pintype "passive"))
    )
    (net (code "21") (name "Net-(CN1-PadD-)") (class "Default")
      (node (ref "CN1") (pin "D-") (pinfunction "D-_D-") (pintype "bidirectional"))
      (node (ref "R4") (pin "1") (pinfunction "1_1") (pintype "passive"))
    )
    (net (code "22") (name "Net-(CN1-PadVBUS)") (class "Default")
      (node (ref "CN1") (pin "VBUS") (pinfunction "VBUS_VBUS") (pintype "power_in"))
      (node (ref "F1") (pin "P$1") (pinfunction "P$1_P$1") (pintype "bidirectional"))
    )
    (net (code "23") (name "Net-(HV_MOD-RADJ)") (class "Default")
      (node (ref "HV_MOD") (pin "2") (pinfunction "RADJ_2") (pintype "bidirectional"))
      (node (ref "R24") (pin "1") (pinfunction "1_1") (pintype "passive"))
    )
    (net (code "24") (name "Net-(IC1-VBAT)") (class "Default")
      (node (ref "BAT1") (pin "POS") (pinfunction "POS_POS") (pintype "bidirectional"))
      (node (ref "IC1") (pin "3") (pinfunction "VBAT_3") (pintype "passive"))
      (node (ref "R11") (pin "1") (pinfunction "1_1") (pintype "passive"))
    )
    (net (code "25") (name "Net-(IC1-X1)") (class "Default")
      (node (ref "IC1") (pin "1") (pinfunction "X1_1") (pintype "input"))
      (node (ref "Y2") (pin "P$2") (pinfunction "2_P$2") (pintype "passive"))
    )
    (net (code "26") (name "Net-(IC1-X2)") (class "Default")
      (node (ref "IC1") (pin "2") (pinfunction "X2_2") (pintype "output"))
      (node (ref "Y2") (pin "P$1") (pinfunction "1_P$1") (pintype "passive"))
    )
    (net (code "27") (name "Net-(IC2-(~{HWB})PE2)") (class "Default")
      (node (ref "IC2") (pin "33") (pinfunction "(~{HWB})PE2_33") (pintype "bidirectional"))
      (node (ref "R12") (pin "2") (pinfunction "2_2") (pintype "passive"))
    )
    (net (code "28") (name "Net-(IC2-AREF)") (class "Default")
      (node (ref "C5") (pin "1") (pinfunction "1_1") (pintype "passive"))
      (node (ref "IC2") (pin "42") (pinfunction "AREF_42") (pintype "bidirectional"))
    )
    (net (code "29") (name "Net-(IC2-UCAP)") (class "Default")
      (node (ref "C4") (pin "1") (pinfunction "1_1") (pintype "passive"))
      (node (ref "IC2") (pin "6") (pinfunction "UCAP_6") (pintype "bidirectional"))
    )
    (net (code "30") (name "Net-(IC3-NC{slash}FB)") (class "Default")
      (node (ref "C9") (pin "1") (pinfunction "1_1") (pintype "passive"))
      (node (ref "IC3") (pin "4") (pinfunction "NC/FB_4") (pintype "bidirectional"))
    )
    (net (code "31") (name "Net-(IC5A-O)") (class "Default")
      (node (ref "IC5") (pin "2") (pinfunction "O_2") (pintype "output"))
      (node (ref "R41") (pin "1") (pinfunction "1_1") (pintype "passive"))
    )
    (net (code "32") (name "Net-(IC5B-O)") (class "Default")
      (node (ref "IC5") (pin "4") (pinfunction "O_4") (pintype "output"))
      (node (ref "R40") (pin "1") (pinfunction "1_1") (pintype "passive"))
    )
    (net (code "33") (name "Net-(IC5C-O)") (class "Default")
      (node (ref "IC5") (pin "6") (pinfunction "O_6") (pintype "output"))
      (node (ref "R39") (pin "1") (pinfunction "1_1") (pintype "passive"))
    )
    (net (code "34") (name "Net-(IC5D-O)") (class "Default")
      (node (ref "IC5") (pin "10") (pinfunction "O_10") (pintype "output"))
      (node (ref "R38") (pin "1") (pinfunction "1_1") (pintype "passive"))
    )
    (net (code "35") (name "Net-(IC5E-I)") (class "Default")
      (node (ref "IC5") (pin "11") (pinfunction "I_11") (pintype "input"))
      (node (ref "R27") (pin "2") (pinfunction "2_2") (pintype "passive"))
    )
    (net (code "36") (name "Net-(IC5F-I)") (class "Default")
      (node (ref "IC5") (pin "14") (pinfunction "I_14") (pintype "input"))
      (node (ref "R28") (pin "2") (pinfunction "2_2") (pintype "passive"))
    )
    (net (code "37") (name "Net-(MOD1-RESERVED_1)") (class "Default")
      (node (ref "MOD1") (pin "2") (pinfunction "RESERVED_1_2") (pintype "bidirectional"))
      (node (ref "TP1") (pin "TP") (pinfunction "TP_TP") (pintype "input"))
    )
    (net (code "38") (name "Net-(MOD1-RESERVED_2)") (class "Default")
      (node (ref "MOD1") (pin "4") (pinfunction "RESERVED_2_4") (pintype "bidirectional"))
      (node (ref "TP2") (pin "TP") (pinfunction "TP_TP") (pintype "input"))
    )
    (net (code "39") (name "Net-(MOD1-RESERVED_3)") (class "Default")
      (node (ref "MOD1") (pin "24") (pinfunction "RESERVED_3_24") (pintype "bidirectional"))
      (node (ref "TP3") (pin "TP") (pinfunction "TP_TP") (pintype "input"))
    )
    (net (code "40") (name "Net-(MOD1-RF_ANT)") (class "Default")
      (node (ref "C13") (pin "1") (pinfunction "1_1") (pintype "passive"))
      (node (ref "MOD1") (pin "35") (pinfunction "RF_ANT_35") (pintype "bidirectional"))
    )
    (net (code "41") (name "Net-(MOD1-SCL_CC3000)") (class "Default")
      (node (ref "MOD1") (pin "30") (pinfunction "SCL_CC3000_30") (pintype "bidirectional"))
      (node (ref "R16") (pin "2") (pinfunction "2_2") (pintype "passive"))
    )
    (net (code "42") (name "Net-(MOD1-SCL_EEPROM)") (class "Default")
      (node (ref "MOD1") (pin "29") (pinfunction "SCL_EEPROM_29") (pintype "bidirectional"))
      (node (ref "R16") (pin "1") (pinfunction "1_1") (pintype "passive"))
    )
    (net (code "43") (name "Net-(MOD1-SDA_CC3000)") (class "Default")
      (node (ref "MOD1") (pin "28") (pinfunction "SDA_CC3000_28") (pintype "bidirectional"))
      (node (ref "R17") (pin "1") (pinfunction "1_1") (pintype "passive"))
    )
    (net (code "44") (name "Net-(MOD1-SDA_EEPROM)") (class "Default")
      (node (ref "MOD1") (pin "27") (pinfunction "SDA_EEPROM_27") (pintype "bidirectional"))
      (node (ref "R17") (pin "2") (pinfunction "2_2") (pintype "passive"))
    )
    (net (code "45") (name "Net-(MOD1-WL_EN1)") (class "Default")
      (node (ref "MOD1") (pin "7") (pinfunction "WL_EN1_7") (pintype "bidirectional"))
      (node (ref "R18") (pin "2") (pinfunction "2_2") (pintype "passive"))
      (node (ref "R19") (pin "1") (pinfunction "1_1") (pintype "passive"))
    )
    (net (code "46") (name "Net-(MOD1-WL_EN2)") (class "Default")
      (node (ref "MOD1") (pin "5") (pinfunction "WL_EN2_5") (pintype "bidirectional"))
      (node (ref "R19") (pin "2") (pinfunction "2_2") (pintype "passive"))
    )
    (net (code "47") (name "Net-(R20-Pad1)") (class "Default")
      (node (ref "R20") (pin "1") (pinfunction "1_1") (pintype "passive"))
      (node (ref "TX") (pin "A") (pinfunction "A_A") (pintype "passive"))
    )
    (net (code "48") (name "Net-(R22-Pad1)") (class "Default")
      (node (ref "R22") (pin "1") (pinfunction "1_1") (pintype "passive"))
      (node (ref "RX") (pin "A") (pinfunction "A_A") (pintype "passive"))
    )
    (net (code "49") (name "Net-(R23-Pad1)") (class "Default")
      (node (ref "R23") (pin "1") (pinfunction "1_1") (pintype "passive"))
      (node (ref "USER") (pin "A") (pinfunction "A_A") (pintype "passive"))
    )
    (net (code "50") (name "Net-(U$2-S)") (class "Default")
      (node (ref "R24") (pin "2") (pinfunction "2_2") (pintype "passive"))
      (node (ref "R25") (pin "2") (pinfunction "2_2") (pintype "passive"))
      (node (ref "U$2") (pin "B") (pinfunction "S_B") (pintype "passive"))
    )
    (net (code "51") (name "RESET") (class "Default")
      (node (ref "C8") (pin "2") (pinfunction "2_2") (pintype "passive"))
      (node (ref "IC2") (pin "13") (pinfunction "RESET_13") (pintype "bidirectional"))
      (node (ref "ISP1") (pin "5") (pinfunction "RESET_5") (pintype "bidirectional"))
      (node (ref "JTAG") (pin "6") (pinfunction "NSRST_6") (pintype "bidirectional"))
      (node (ref "R1") (pin "1") (pinfunction "1_1") (pintype "passive"))
      (node (ref "RESET") (pin "A") (pinfunction "P$1_A") (pintype "bidirectional"))
      (node (ref "RESET") (pin "B") (pinfunction "P$1_B") (pintype "bidirectional"))
    )
    (net (code "52") (name "RTC_ADC") (class "Default")
      (node (ref "C7") (pin "1") (pinfunction "1_1") (pintype "passive"))
      (node (ref "IC2") (pin "41") (pinfunction "(ADC0)PF0_41") (pintype "bidirectional"))
      (node (ref "R11") (pin "2") (pinfunction "2_2") (pintype "passive"))
    )
    (net (code "53") (name "RTC_SCL") (class "Default")
      (node (ref "IC1") (pin "6") (pinfunction "SCL_6") (pintype "input"))
      (node (ref "R10") (pin "1") (pinfunction "1_1") (pintype "passive"))
    )
    (net (code "54") (name "RTC_SDA") (class "Default")
      (node (ref "IC1") (pin "5") (pinfunction "SDA_5") (pintype "bidirectional"))
      (node (ref "R9") (pin "1") (pinfunction "1_1") (pintype "passive"))
    )
    (net (code "55") (name "RXLED") (class "Default")
      (node (ref "IC2") (pin "8") (pinfunction "(SS/PCINT0)PB0_8") (pintype "bidirectional"))
      (node (ref "RX") (pin "C") (pinfunction "C_C") (pintype "passive"))
    )
    (net (code "56") (name "SPI_MISO") (class "Default")
      (node (ref "IC2") (pin "11") (pinfunction "(PDO/PCINT3/MISO)PB3_11") (pintype "bidirectional"))
      (node (ref "ISP1") (pin "1") (pinfunction "MISO_1") (pintype "bidirectional"))
      (node (ref "R37") (pin "1") (pinfunction "1_1") (pintype "passive"))
    )
    (net (code "57") (name "SPI_MOSI") (class "Default")
      (node (ref "IC2") (pin "10") (pinfunction "(PDI/PCINT2/MOSI)PB2_10") (pintype "bidirectional"))
      (node (ref "IC5") (pin "7") (pinfunction "I_7") (pintype "input"))
      (node (ref "ISP1") (pin "4") (pinfunction "MOSI_4") (pintype "bidirectional"))
      (node (ref "R33") (pin "2") (pinfunction "2_2") (pintype "passive"))
    )
    (net (code "58") (name "SPI_SCLK") (class "Default")
      (node (ref "IC2") (pin "9") (pinfunction "(PCINT1/SCLK)PB1_9") (pintype "bidirectional"))
      (node (ref "IC5") (pin "5") (pinfunction "I_5") (pintype "input"))
      (node (ref "ISP1") (pin "3") (pinfunction "SCK_3") (pintype "bidirectional"))
      (node (ref "R30") (pin "1") (pinfunction "1_1") (pintype "passive"))
    )
    (net (code "59") (name "SR_EN") (class "Default")
      (node (ref "JP2") (pin "1") (pinfunction "1_1") (pintype "passive"))
      (node (ref "R29") (pin "2") (pinfunction "2_2") (pintype "passive"))
    )
    (net (code "60") (name "SR_MOSI") (class "Default")
      (node (ref "JP2") (pin "4") (pinfunction "4_4") (pintype "passive"))
      (node (ref "R33") (pin "1") (pinfunction "1_1") (pintype "passive"))
    )
    (net (code "61") (name "SR_RCK") (class "Default")
      (node (ref "JP2") (pin "5") (pinfunction "5_5") (pintype "passive"))
      (node (ref "R31") (pin "2") (pinfunction "2_2") (pintype "passive"))
    )
    (net (code "62") (name "SR_SCK") (class "Default")
      (node (ref "JP2") (pin "3") (pinfunction "3_3") (pintype "passive"))
      (node (ref "R30") (pin "2") (pinfunction "2_2") (pintype "passive"))
    )
    (net (code "63") (name "SR_SCL") (class "Default")
      (node (ref "JP2") (pin "2") (pinfunction "2_2") (pintype "passive"))
      (node (ref "R32") (pin "1") (pinfunction "1_1") (pintype "passive"))
    )
    (net (code "64") (name "TRS_3V3") (class "Default")
      (node (ref "C10") (pin "1") (pinfunction "1_1") (pintype "passive"))
      (node (ref "IC3") (pin "5") (pinfunction "OUT_5") (pintype "bidirectional"))
      (node (ref "R13") (pin "2") (pinfunction "2_2") (pintype "passive"))
      (node (ref "R14") (pin "2") (pinfunction "2_2") (pintype "passive"))
      (node (ref "U$3") (pin "1") (pinfunction "1_1") (pintype "bidirectional"))
    )
    (net (code "65") (name "TRS_3V3_EN") (class "Default")
      (node (ref "IC2") (pin "30") (pinfunction "(PCINT6/OC1B/OC4B/ADC13)PB6_30") (pintype "bidirectional"))
      (node (ref "IC3") (pin "3") (pinfunction "ON/~{OFF}_3") (pintype "bidirectional"))
      (node (ref "R15") (pin "2") (pinfunction "2_2") (pintype "passive"))
    )
    (net (code "66") (name "TRS_DCF77") (class "Default")
      (node (ref "R13") (pin "1") (pinfunction "1_1") (pintype "passive"))
      (node (ref "R28") (pin "1") (pinfunction "1_1") (pintype "passive"))
      (node (ref "U$3") (pin "3") (pinfunction "3_3") (pintype "bidirectional"))
    )
    (net (code "67") (name "TRS_GPS") (class "Default")
      (node (ref "R14") (pin "1") (pinfunction "1_1") (pintype "passive"))
      (node (ref "R27") (pin "1") (pinfunction "1_1") (pintype "passive"))
      (node (ref "U$3") (pin "4") (pinfunction "4_4") (pintype "bidirectional"))
      (node (ref "U$3") (pin "4-2") (pinfunction "4_4-2") (pintype "bidirectional"))
    )
    (net (code "68") (name "TXLED") (class "Default")
      (node (ref "IC2") (pin "22") (pinfunction "(XCK1/~{CTS})PD5_22") (pintype "bidirectional"))
      (node (ref "TX") (pin "C") (pinfunction "C_C") (pintype "passive"))
    )
    (net (code "69") (name "UART_RX") (class "Default")
      (node (ref "IC2") (pin "20") (pinfunction "(RXD1/INT2)PD2_20") (pintype "bidirectional"))
      (node (ref "IC5") (pin "12") (pinfunction "O_12") (pintype "output"))
      (node (ref "TP9") (pin "TP") (pinfunction "TP_TP") (pintype "input"))
    )
    (net (code "70") (name "UART_TX") (class "Default")
      (node (ref "IC2") (pin "21") (pinfunction "(TXD1/INT3)PD3_21") (pintype "bidirectional"))
      (node (ref "TP7") (pin "TP") (pinfunction "TP_TP") (pintype "input"))
    )
    (net (code "71") (name "UC_DCF77") (class "Default")
      (node (ref "IC2") (pin "12") (pinfunction "(PCINT7/OC0A/OC1C/~{RTS})PB7_12") (pintype "bidirectional"))
      (node (ref "IC5") (pin "15") (pinfunction "O_15") (pintype "output"))
    )
    (net (code "72") (name "VBUS") (class "Default")
      (node (ref "IC2") (pin "7") (pinfunction "VBUS_7") (pintype "bidirectional"))
    )
    (net (code "73") (name "VDD") (class "Default")
      (node (ref "HV_MOD") (pin "1") (pinfunction "HVOUT_1") (pintype "bidirectional"))
      (node (ref "JP1") (pin "1") (pinfunction "1_1") (pintype "passive"))
      (node (ref "R2") (pin "2") (pinfunction "2_2") (pintype "passive"))
    )
    (net (code "74") (name "WIFI_CS") (class "Default")
      (node (ref "IC2") (pin "26") (pinfunction "(T1/~{OC4D}/ADC9)PD6_26") (pintype "bidirectional"))
      (node (ref "IC5") (pin "9") (pinfunction "I_9") (pintype "input"))
    )
    (net (code "75") (name "WIFI_EN") (class "Default")
      (node (ref "IC2") (pin "25") (pinfunction "(ICP1/ADC8)PD4_25") (pintype "bidirectional"))
      (node (ref "IC5") (pin "3") (pinfunction "I_3") (pintype "input"))
    )
    (net (code "76") (name "WIFI_IRQ") (class "Default")
      (node (ref "IC2") (pin "1") (pinfunction "(INT.6/AIN0)PE6_1") (pintype "bidirectional"))
      (node (ref "R26") (pin "1") (pinfunction "1_1") (pintype "passive"))
    )
    (net (code "77") (name "WL_3V3") (class "Default")
      (node (ref "C14") (pin "1") (pinfunction "1_1") (pintype "passive"))
      (node (ref "C15") (pin "1") (pinfunction "1_1") (pintype "passive"))
      (node (ref "C16") (pin "1") (pinfunction "1_1") (pintype "passive"))
      (node (ref "C18") (pin "1") (pinfunction "1_1") (pintype "passive"))
      (node (ref "IC4") (pin "2") (pinfunction "OUT_2") (pintype "passive"))
      (node (ref "IC4") (pin "4") (pinfunction "OUT_4") (pintype "passive"))
      (node (ref "IC5") (pin "1") (pinfunction "VDD_1") (pintype "power_in"))
      (node (ref "MOD1") (pin "19") (pinfunction "VBAT_IN_19") (pintype "bidirectional"))
      (node (ref "MOD1") (pin "23") (pinfunction "VIO_HOST_23") (pintype "bidirectional"))
    )
    (net (code "78") (name "WL_EN") (class "Default")
      (node (ref "MOD1") (pin "26") (pinfunction "VBAT_SW_EN_26") (pintype "bidirectional"))
      (node (ref "R41") (pin "2") (pinfunction "2_2") (pintype "passive"))
    )
    (net (code "79") (name "WL_SPI_CLK") (class "Default")
      (node (ref "MOD1") (pin "17") (pinfunction "SPI_CLK_17") (pintype "bidirectional"))
      (node (ref "R40") (pin "2") (pinfunction "2_2") (pintype "passive"))
    )
    (net (code "80") (name "WL_SPI_CS") (class "Default")
      (node (ref "MOD1") (pin "12") (pinfunction "SPI_CS_12") (pintype "bidirectional"))
      (node (ref "R38") (pin "2") (pinfunction "2_2") (pintype "passive"))
    )
    (net (code "81") (name "WL_SPI_DIN") (class "Default")
      (node (ref "MOD1") (pin "15") (pinfunction "SPI_DIN_15") (pintype "bidirectional"))
      (node (ref "R39") (pin "2") (pinfunction "2_2") (pintype "passive"))
    )
    (net (code "82") (name "WL_SPI_DOUT") (class "Default")
      (node (ref "MOD1") (pin "13") (pinfunction "SPI_DOUT_13") (pintype "bidirectional"))
      (node (ref "R37") (pin "2") (pinfunction "2_2") (pintype "passive"))
    )
    (net (code "83") (name "WL_SPI_IRQ") (class "Default")
      (node (ref "MOD1") (pin "14") (pinfunction "SPI_IRQ_14") (pintype "bidirectional"))
      (node (ref "R26") (pin "2") (pinfunction "2_2") (pintype "passive"))
    )
    (net (code "84") (name "WL_UART_RX") (class "Default")
      (node (ref "MOD1") (pin "8") (pinfunction "WL_RS232_RX_8") (pintype "bidirectional"))
      (node (ref "TP5") (pin "TP") (pinfunction "TP_TP") (pintype "input"))
    )
    (net (code "85") (name "WL_UART_TX") (class "Default")
      (node (ref "MOD1") (pin "6") (pinfunction "WL_RS232_TX_6") (pintype "bidirectional"))
      (node (ref "TP4") (pin "TP") (pinfunction "TP_TP") (pintype "input"))
    )
    (net (code "86") (name "XTAL1") (class "Default")
      (node (ref "C2") (pin "2") (pinfunction "2_2") (pintype "passive"))
      (node (ref "IC2") (pin "17") (pinfunction "XTAL1_17") (pintype "bidirectional"))
      (node (ref "Y1") (pin "CRYSTAL2") (pinfunction "CRYSTAL2_CRYSTAL2") (pintype "bidirectional"))
    )
    (net (code "87") (name "XTAL2") (class "Default")
      (node (ref "C1") (pin "2") (pinfunction "2_2") (pintype "passive"))
      (node (ref "IC2") (pin "16") (pinfunction "XTAL2_16") (pintype "bidirectional"))
      (node (ref "Y1") (pin "CRYSTAL1") (pinfunction "CRYSTAL1_CRYSTAL1") (pintype "bidirectional"))
    )
    (net (code "88") (name "unconnected-(ANT1-PadMOUNT)") (class "Default")
      (node (ref "ANT1") (pin "MOUNT") (pinfunction "MOUNT_MOUNT") (pintype "bidirectional"))
    )
    (net (code "89") (name "unconnected-(CN1-PadID)") (class "Default")
      (node (ref "CN1") (pin "ID") (pinfunction "ID_ID") (pintype "bidirectional"))
    )
    (net (code "90") (name "unconnected-(HV_MOD-VBIAS-Pad6)") (class "Default")
      (node (ref "HV_MOD") (pin "6") (pinfunction "VBIAS_6") (pintype "bidirectional"))
    )
    (net (code "91") (name "unconnected-(IC1-SQW-Pad7)") (class "Default")
      (node (ref "IC1") (pin "7") (pinfunction "SQW_7") (pintype "open_collector"))
    )
    (net (code "92") (name "unconnected-(JTAG-NTRST-Pad8)") (class "Default")
      (node (ref "JTAG") (pin "8") (pinfunction "NTRST_8") (pintype "bidirectional"))
    )
    (net (code "93") (name "unconnected-(JTAG-VCC-Pad7)") (class "Default")
      (node (ref "JTAG") (pin "7") (pinfunction "VCC_7") (pintype "bidirectional"))
    )
    (net (code "94") (name "unconnected-(U$2-PadA)") (class "Default")
      (node (ref "U$2") (pin "A") (pinfunction "A_A") (pintype "passive"))
    )
  )
)
